# TIDA-010954-Output.net
KiCad netlist of a schematic drawn in Altium Designer
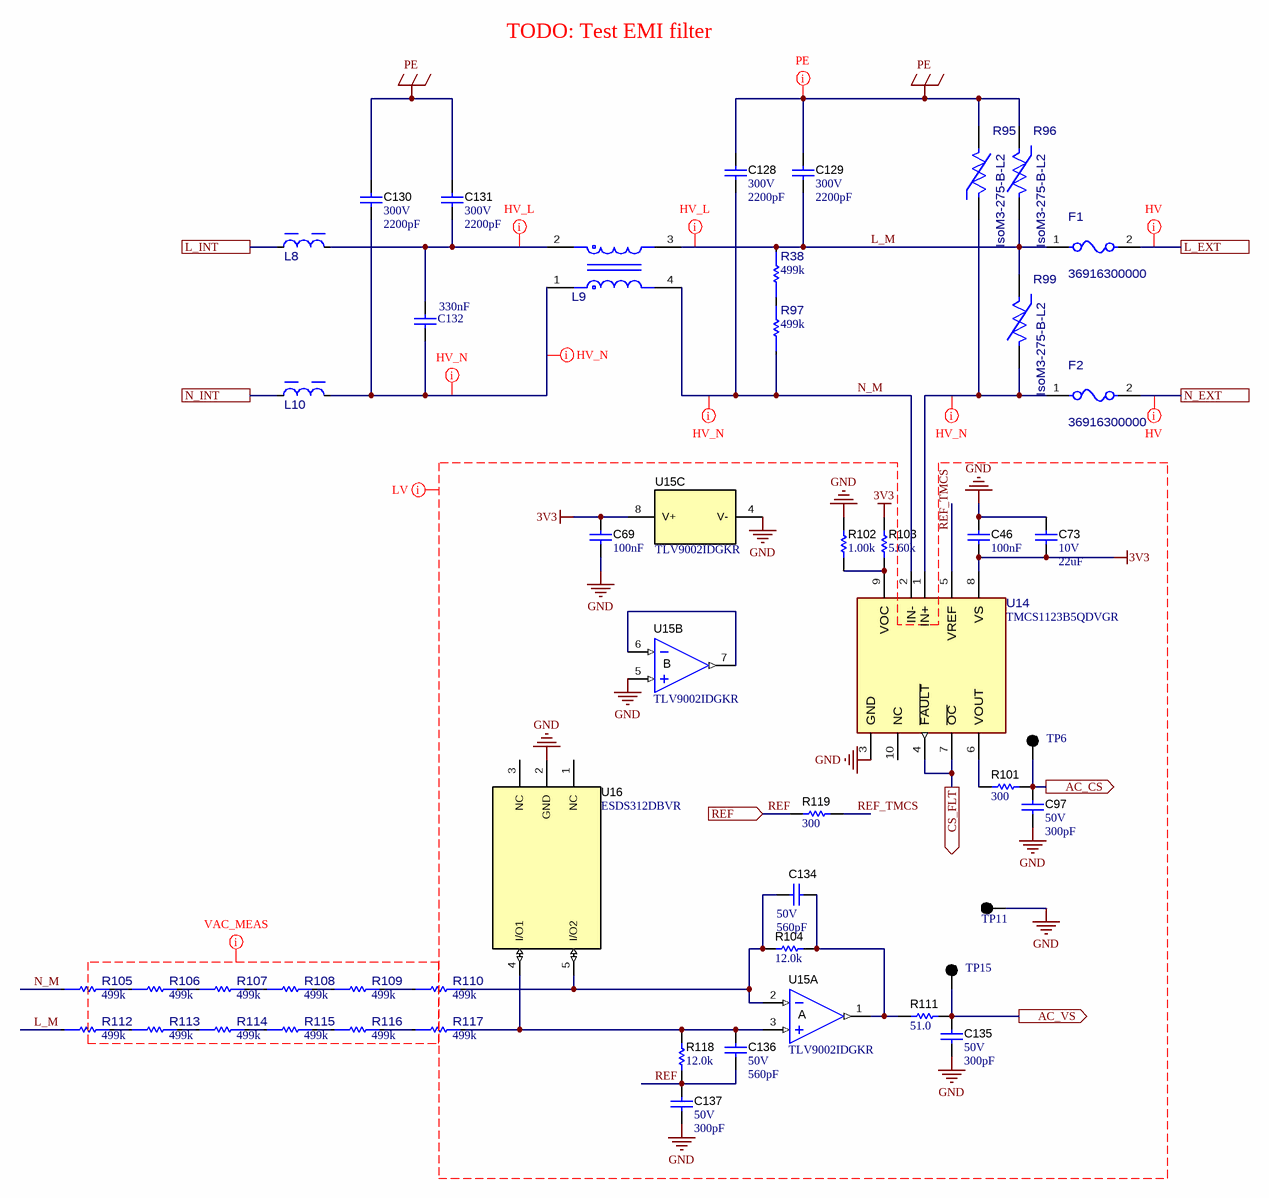
[diagram p0: TIDA-010954-Output.SchDoc]

(export (version "E")
  (design (tool "Eeschema 10.0.6"))
  (components
    (comp (ref "C46")
      (value "CGA3E2X7R1E104K080AA")
      (footprint "0603")
      (description "CAP, CERM, 0.1 uF, 25 V, +/- 10%, X7R, AEC-Q200 Grade 1, 0603")
      (fields
        (field (name "MANUFACTURER") "TDK")
        (field (name "CAP_F") "100nF")
        (field (name "PUBLISHER") "Texas Instruments")
      )
      (libsource (lib "Altium Vault - TI") (part "Capacitor"))
    )
    (comp (ref "C69")
      (value "CGA3E2X7R1E104K080AA")
      (footprint "0603")
      (description "CAP, CERM, 0.1 uF, 25 V, +/- 10%, X7R, AEC-Q200 Grade 1, 0603")
      (fields
        (field (name "MANUFACTURER") "TDK")
        (field (name "CAP_F") "100nF")
        (field (name "PUBLISHER") "Texas Instruments")
      )
      (libsource (lib "Altium Vault - TI") (part "Capacitor"))
    )
    (comp (ref "C73")
      (value "GRM31CR71A226KE15L")
      (footprint "1206_180")
      (description "CAP, CERM, 22 uF, 10 V, +/- 10%, X7R, 1206")
      (fields
        (field (name "MANUFACTURER") "MuRata")
        (field (name "VDC_V") "10V")
        (field (name "VALUEDISPLAYED") "22uF")
        (field (name "PUBLISHER") "Texas Instruments")
      )
      (libsource (lib "Altium Vault - TI") (part "Capacitor"))
    )
    (comp (ref "C97")
      (value "GRM1885C1H301JA01D")
      (footprint "0603")
      (description "CAP, CERM, 300 pF, 50 V, +/- 5%, C0G/NP0, 0603")
      (fields
        (field (name "MANUFACTURER") "MuRata")
        (field (name "VDC_V") "50V")
        (field (name "VALUEDISPLAYED") "300pF")
        (field (name "PUBLISHER") "Texas Instruments")
      )
      (libsource (lib "Altium Vault - TI") (part "Capacitor"))
    )
    (comp (ref "C128")
      (value "DE6E3KJ222MN3A")
      (footprint "E_900x700x900")
      (description "CAP, CERM, 2200 pF, 300 V, +/- 20%, E, TH, 2- Leads, Body 9x7mm, Pin Spacing 7.5mm")
      (fields
        (field (name "MANUFACTURER") "MuRata")
        (field (name "VDC_V") "300V")
        (field (name "VALUEDISPLAYED") "2200pF")
        (field (name "PUBLISHER") "Texas Instruments")
      )
      (libsource (lib "Altium Vault - TI") (part "Capacitor"))
    )
    (comp (ref "C129")
      (value "DE6E3KJ222MN3A")
      (footprint "E_900x700x900")
      (description "CAP, CERM, 2200 pF, 300 V, +/- 20%, E, TH, 2- Leads, Body 9x7mm, Pin Spacing 7.5mm")
      (fields
        (field (name "MANUFACTURER") "MuRata")
        (field (name "VDC_V") "300V")
        (field (name "VALUEDISPLAYED") "2200pF")
        (field (name "PUBLISHER") "Texas Instruments")
      )
      (libsource (lib "Altium Vault - TI") (part "Capacitor"))
    )
    (comp (ref "C130")
      (value "DE6E3KJ222MN3A")
      (footprint "E_900x700x900")
      (description "CAP, CERM, 2200 pF, 300 V, +/- 20%, E, TH, 2- Leads, Body 9x7mm, Pin Spacing 7.5mm")
      (fields
        (field (name "MANUFACTURER") "MuRata")
        (field (name "VDC_V") "300V")
        (field (name "VALUEDISPLAYED") "2200pF")
        (field (name "PUBLISHER") "Texas Instruments")
      )
      (libsource (lib "Altium Vault - TI") (part "Capacitor"))
    )
    (comp (ref "C131")
      (value "DE6E3KJ222MN3A")
      (footprint "E_900x700x900")
      (description "CAP, CERM, 2200 pF, 300 V, +/- 20%, E, TH, 2- Leads, Body 9x7mm, Pin Spacing 7.5mm")
      (fields
        (field (name "MANUFACTURER") "MuRata")
        (field (name "VDC_V") "300V")
        (field (name "VALUEDISPLAYED") "2200pF")
        (field (name "PUBLISHER") "Texas Instruments")
      )
      (libsource (lib "Altium Vault - TI") (part "Capacitor"))
    )
    (comp (ref "C132")
      (value "890324025034CS")
      (footprint "WCAP-FTX2_L18W8.5H14.5_CS")
      (description "WCAP-FTX2 Film Capacitor, THT, L18 x W8.5 x H14.5mm, 330nF, 275V")
      (fields (field (name "CAP_F") "330nF") (field (name "MANUFACTURER") "Wurth Elektronik"))
      (libsource (lib "Altium Vault - TI") (part "890764429002CS"))
    )
    (comp (ref "C134")
      (value "GRM1885C1H561JA01D")
      (footprint "0603")
      (description "CAP, CERM, 560 pF, 50 V, +/- 5%, C0G/NP0, 0603")
      (fields
        (field (name "MANUFACTURER") "MuRata")
        (field (name "VDC_V") "50V")
        (field (name "VALUEDISPLAYED") "560pF")
        (field (name "PUBLISHER") "Texas Instruments")
      )
      (libsource (lib "Altium Vault - TI") (part "Capacitor"))
    )
    (comp (ref "C135")
      (value "GRM1885C1H301JA01D")
      (footprint "0603")
      (description "CAP, CERM, 300 pF, 50 V, +/- 5%, C0G/NP0, 0603")
      (fields
        (field (name "MANUFACTURER") "MuRata")
        (field (name "VDC_V") "50V")
        (field (name "VALUEDISPLAYED") "300pF")
        (field (name "PUBLISHER") "Texas Instruments")
      )
      (libsource (lib "Altium Vault - TI") (part "Capacitor"))
    )
    (comp (ref "C136")
      (value "GRM1885C1H561JA01D")
      (footprint "0603")
      (description "CAP, CERM, 560 pF, 50 V, +/- 5%, C0G/NP0, 0603")
      (fields
        (field (name "MANUFACTURER") "MuRata")
        (field (name "VDC_V") "50V")
        (field (name "VALUEDISPLAYED") "560pF")
        (field (name "PUBLISHER") "Texas Instruments")
      )
      (libsource (lib "Altium Vault - TI") (part "Capacitor"))
    )
    (comp (ref "C137")
      (value "GRM1885C1H301JA01D")
      (footprint "0603")
      (description "CAP, CERM, 300 pF, 50 V, +/- 5%, C0G/NP0, 0603")
      (fields
        (field (name "MANUFACTURER") "MuRata")
        (field (name "VDC_V") "50V")
        (field (name "VALUEDISPLAYED") "300pF")
        (field (name "PUBLISHER") "Texas Instruments")
      )
      (libsource (lib "Altium Vault - TI") (part "Capacitor"))
    )
    (comp (ref "F1")
      (value "36916300000")
      (footprint "FP-36916300000_RADIAL-MFG")
      (description "6.3 A 300 V AC DC Fuse Board Mount (Cartridge Style Excluded) Through Hole Radial, Box")
      (fields
        (field (name "MANUFACTURER") "Littelfuse Inc")
        (field (name "DIGIKEY PART NUMBER") "F5465CT-ND")
      )
      (libsource (lib "Altium Vault - TI") (part "SYM-36916300000"))
    )
    (comp (ref "F2")
      (value "36916300000")
      (footprint "FP-36916300000_RADIAL-MFG")
      (description "6.3 A 300 V AC DC Fuse Board Mount (Cartridge Style Excluded) Through Hole Radial, Box")
      (fields
        (field (name "MANUFACTURER") "Littelfuse Inc")
        (field (name "DIGIKEY PART NUMBER") "F5465CT-ND")
      )
      (libsource (lib "Altium Vault - TI") (part "SYM-36916300000"))
    )
    (comp (ref "L8")
      (value "7443551221")
      (footprint "FP-7443551221_SMD_IND_12MM8_12MM8-MFG")
      (description "22 µH Shielded Wirewound Inductor 6 A 24.7mOhm Nonstandard")
      (fields
        (field (name "MANUFACTURER") "Wurth Electronics")
        (field (name "MOUSER PART NUMBER") "710-7443551221")
      )
      (libsource (lib "Altium Vault - TI") (part "SYM-7443551221"))
    )
    (comp (ref "L9")
      (value "7448025003")
      (footprint "FP-7448025003_PTH_COMMON_CHOKE-MFG")
      (description "2.5 mH @ 10 kHz 2 Line Common Mode Choke Through Hole 5A DCR 15mOhm")
      (fields
        (field (name "MOUSER PART NUMBER") "710-7448025003")
        (field (name "DIGIKEY PART NUMBER") "732-13592-ND")
      )
      (libsource (lib "Altium Vault - TI") (part "SYM-7448025003"))
    )
    (comp (ref "L10")
      (value "7443551221")
      (footprint "FP-7443551221_SMD_IND_12MM8_12MM8-MFG")
      (description "22 µH Shielded Wirewound Inductor 6 A 24.7mOhm Nonstandard")
      (fields
        (field (name "MANUFACTURER") "Wurth Electronics")
        (field (name "MOUSER PART NUMBER") "710-7443551221")
      )
      (libsource (lib "Altium Vault - TI") (part "SYM-7443551221"))
    )
    (comp (ref "R38")
      (value "499k")
      (footprint "FP-ERJP08D4993V_1206-MFG")
      (fields
        (field (name "MANUFACTURER") "Panasonic")
        (field (name "PARTNUMBER") "ERJP08D4993V")
        (field (name "DIGIKEY PART NUMBER") "ERJ-P08D4993V-ND")
      )
      (libsource (lib "Altium Vault - TI") (part "SYM-ERJP08D4993V"))
    )
    (comp (ref "R95")
      (value "IsoM3-275-B-L2")
      (footprint "FP-IsoM3-275-B-L2_RADIAL-MFG")
      (description "3 kA Varistor 1 Circuit Through Hole Disc 13.2mm")
      (fields
        (field (name "DIGIKEY PART NUMBER") "118-ISOM3-275-B-L2-ND")
        (field (name "MANUFACTURER") "Bourns")
      )
      (libsource (lib "Altium Vault - TI") (part "SYM-IsoM3-275-B-L2"))
    )
    (comp (ref "R96")
      (value "IsoM3-275-B-L2")
      (footprint "FP-IsoM3-275-B-L2_RADIAL-MFG")
      (description "3 kA Varistor 1 Circuit Through Hole Disc 13.2mm")
      (fields
        (field (name "DIGIKEY PART NUMBER") "118-ISOM3-275-B-L2-ND")
        (field (name "MANUFACTURER") "Bourns")
      )
      (libsource (lib "Altium Vault - TI") (part "SYM-IsoM3-275-B-L2"))
    )
    (comp (ref "R97")
      (value "499k")
      (footprint "FP-ERJP08D4993V_1206-MFG")
      (fields
        (field (name "MANUFACTURER") "Panasonic")
        (field (name "PARTNUMBER") "ERJP08D4993V")
        (field (name "DIGIKEY PART NUMBER") "ERJ-P08D4993V-ND")
      )
      (libsource (lib "Altium Vault - TI") (part "SYM-ERJP08D4993V"))
    )
    (comp (ref "R99")
      (value "IsoM3-275-B-L2")
      (footprint "FP-IsoM3-275-B-L2_RADIAL-MFG")
      (description "3 kA Varistor 1 Circuit Through Hole Disc 13.2mm")
      (fields
        (field (name "DIGIKEY PART NUMBER") "118-ISOM3-275-B-L2-ND")
        (field (name "MANUFACTURER") "Bourns")
      )
      (libsource (lib "Altium Vault - TI") (part "SYM-IsoM3-275-B-L2"))
    )
    (comp (ref "R101")
      (value "RC0603FR-07300RL")
      (footprint "0603")
      (description "RES, 300, 1%, 0.1 W, 0603")
      (fields (field (name "MANUFACTURER") "Yageo") (field (name "VALUEDISPLAYED") "300"))
      (libsource (lib "Altium Vault - TI") (part "Resistor"))
    )
    (comp (ref "R102")
      (value "RC0603FR-071KL")
      (footprint "0603")
      (description "RES, 1.00 k, 1%, 0.1 W, 0603")
      (fields (field (name "MANUFACTURER") "Yageo") (field (name "VALUEDISPLAYED") "1.00k"))
      (libsource (lib "Altium Vault - TI") (part "Resistor"))
    )
    (comp (ref "R103")
      (value "RC0603FR-075K6L")
      (footprint "0603")
      (description "RES, 5.60 k, 1%, 0.1 W, 0603")
      (fields (field (name "MANUFACTURER") "Yageo") (field (name "VALUEDISPLAYED") "5.60k"))
      (libsource (lib "Altium Vault - TI") (part "Resistor"))
    )
    (comp (ref "R104")
      (value "RT0603BRD0712KL")
      (footprint "0603")
      (description "RES, 12.0 k, 0.1%, 0.1 W, 0603")
      (fields
        (field (name "MANUFACTURER") "Yageo America")
        (field (name "VALUEDISPLAYED") "12.0k")
        (field (name "PUBLISHER") "Texas Instruments")
      )
      (libsource (lib "Altium Vault - TI") (part "Resistor"))
    )
    (comp (ref "R105")
      (value "499k")
      (footprint "FP-ERJP08D4993V_1206-MFG")
      (fields
        (field (name "MANUFACTURER") "Panasonic")
        (field (name "PARTNUMBER") "ERJP08D4993V")
        (field (name "DIGIKEY PART NUMBER") "ERJ-P08D4993V-ND")
      )
      (libsource (lib "Altium Vault - TI") (part "SYM-ERJP08D4993V"))
    )
    (comp (ref "R106")
      (value "499k")
      (footprint "FP-ERJP08D4993V_1206-MFG")
      (fields
        (field (name "MANUFACTURER") "Panasonic")
        (field (name "PARTNUMBER") "ERJP08D4993V")
        (field (name "DIGIKEY PART NUMBER") "ERJ-P08D4993V-ND")
      )
      (libsource (lib "Altium Vault - TI") (part "SYM-ERJP08D4993V"))
    )
    (comp (ref "R107")
      (value "499k")
      (footprint "FP-ERJP08D4993V_1206-MFG")
      (fields
        (field (name "MANUFACTURER") "Panasonic")
        (field (name "PARTNUMBER") "ERJP08D4993V")
        (field (name "DIGIKEY PART NUMBER") "ERJ-P08D4993V-ND")
      )
      (libsource (lib "Altium Vault - TI") (part "SYM-ERJP08D4993V"))
    )
    (comp (ref "R108")
      (value "499k")
      (footprint "FP-ERJP08D4993V_1206-MFG")
      (fields
        (field (name "MANUFACTURER") "Panasonic")
        (field (name "PARTNUMBER") "ERJP08D4993V")
        (field (name "DIGIKEY PART NUMBER") "ERJ-P08D4993V-ND")
      )
      (libsource (lib "Altium Vault - TI") (part "SYM-ERJP08D4993V"))
    )
    (comp (ref "R109")
      (value "499k")
      (footprint "FP-ERJP08D4993V_1206-MFG")
      (fields
        (field (name "MANUFACTURER") "Panasonic")
        (field (name "PARTNUMBER") "ERJP08D4993V")
        (field (name "DIGIKEY PART NUMBER") "ERJ-P08D4993V-ND")
      )
      (libsource (lib "Altium Vault - TI") (part "SYM-ERJP08D4993V"))
    )
    (comp (ref "R110")
      (value "499k")
      (footprint "FP-ERJP08D4993V_1206-MFG")
      (fields
        (field (name "MANUFACTURER") "Panasonic")
        (field (name "PARTNUMBER") "ERJP08D4993V")
        (field (name "DIGIKEY PART NUMBER") "ERJ-P08D4993V-ND")
      )
      (libsource (lib "Altium Vault - TI") (part "SYM-ERJP08D4993V"))
    )
    (comp (ref "R111")
      (value "RC0603FR-0751RL")
      (footprint "0603")
      (description "RES, 51.0, 1%, 0.1 W, 0603")
      (fields (field (name "MANUFACTURER") "Yageo") (field (name "VALUEDISPLAYED") "51.0"))
      (libsource (lib "Altium Vault - TI") (part "Resistor"))
    )
    (comp (ref "R112")
      (value "499k")
      (footprint "FP-ERJP08D4993V_1206-MFG")
      (fields
        (field (name "MANUFACTURER") "Panasonic")
        (field (name "PARTNUMBER") "ERJP08D4993V")
        (field (name "DIGIKEY PART NUMBER") "ERJ-P08D4993V-ND")
      )
      (libsource (lib "Altium Vault - TI") (part "SYM-ERJP08D4993V"))
    )
    (comp (ref "R113")
      (value "499k")
      (footprint "FP-ERJP08D4993V_1206-MFG")
      (fields
        (field (name "MANUFACTURER") "Panasonic")
        (field (name "PARTNUMBER") "ERJP08D4993V")
        (field (name "DIGIKEY PART NUMBER") "ERJ-P08D4993V-ND")
      )
      (libsource (lib "Altium Vault - TI") (part "SYM-ERJP08D4993V"))
    )
    (comp (ref "R114")
      (value "499k")
      (footprint "FP-ERJP08D4993V_1206-MFG")
      (fields
        (field (name "MANUFACTURER") "Panasonic")
        (field (name "PARTNUMBER") "ERJP08D4993V")
        (field (name "DIGIKEY PART NUMBER") "ERJ-P08D4993V-ND")
      )
      (libsource (lib "Altium Vault - TI") (part "SYM-ERJP08D4993V"))
    )
    (comp (ref "R115")
      (value "499k")
      (footprint "FP-ERJP08D4993V_1206-MFG")
      (fields
        (field (name "MANUFACTURER") "Panasonic")
        (field (name "PARTNUMBER") "ERJP08D4993V")
        (field (name "DIGIKEY PART NUMBER") "ERJ-P08D4993V-ND")
      )
      (libsource (lib "Altium Vault - TI") (part "SYM-ERJP08D4993V"))
    )
    (comp (ref "R116")
      (value "499k")
      (footprint "FP-ERJP08D4993V_1206-MFG")
      (fields
        (field (name "MANUFACTURER") "Panasonic")
        (field (name "PARTNUMBER") "ERJP08D4993V")
        (field (name "DIGIKEY PART NUMBER") "ERJ-P08D4993V-ND")
      )
      (libsource (lib "Altium Vault - TI") (part "SYM-ERJP08D4993V"))
    )
    (comp (ref "R117")
      (value "499k")
      (footprint "FP-ERJP08D4993V_1206-MFG")
      (fields
        (field (name "MANUFACTURER") "Panasonic")
        (field (name "PARTNUMBER") "ERJP08D4993V")
        (field (name "DIGIKEY PART NUMBER") "ERJ-P08D4993V-ND")
      )
      (libsource (lib "Altium Vault - TI") (part "SYM-ERJP08D4993V"))
    )
    (comp (ref "R118")
      (value "RT0603BRD0712KL")
      (footprint "0603")
      (description "RES, 12.0 k, 0.1%, 0.1 W, 0603")
      (fields
        (field (name "MANUFACTURER") "Yageo America")
        (field (name "VALUEDISPLAYED") "12.0k")
        (field (name "PUBLISHER") "Texas Instruments")
      )
      (libsource (lib "Altium Vault - TI") (part "Resistor"))
    )
    (comp (ref "R119")
      (value "RC0603FR-07300RL")
      (footprint "0603")
      (description "RES, 300, 1%, 0.1 W, 0603")
      (fields (field (name "MANUFACTURER") "Yageo") (field (name "VALUEDISPLAYED") "300"))
      (libsource (lib "Altium Vault - TI") (part "Resistor"))
    )
    (comp (ref "TP6")
      (value "5011")
      (footprint "Keystone5011")
      (description "Test Point, Multipurpose, Black, TH")
      (fields
        (field (name "MANUFACTURER") "Keystone Electronics")
        (field (name "PUBLISHER") "Texas Instruments")
      )
      (libsource (lib "Altium Vault - TI") (part "5011"))
    )
    (comp (ref "TP11")
      (value "5011")
      (footprint "Keystone5011")
      (description "Test Point, Multipurpose, Black, TH")
      (fields
        (field (name "MANUFACTURER") "Keystone Electronics")
        (field (name "PUBLISHER") "Texas Instruments")
      )
      (libsource (lib "Altium Vault - TI") (part "5011"))
    )
    (comp (ref "TP15")
      (value "5011")
      (footprint "Keystone5011")
      (description "Test Point, Multipurpose, Black, TH")
      (fields
        (field (name "MANUFACTURER") "Keystone Electronics")
        (field (name "PUBLISHER") "Texas Instruments")
      )
      (libsource (lib "Altium Vault - TI") (part "5011"))
    )
    (comp (ref "U14")
      (value "TMCS1123B5QDVGR")
      (footprint "DVG0010A-MFG")
      (fields (field (name "PARTNUMBER") "TMCS1123B5QDVGR") (field (name "MANUFACTURER") "Texas Instruments"))
      (libsource (lib "Altium Vault - TI") (part "SYM-TMCS1123B5QDVGR"))
    )
    (comp (ref "U15")
      (value "TLV9002IDGKR")
      (footprint "DGK0008A_N")
      (fields
        (field (name "ALTERNATE PARTNUMBER") "TLV2333IDGKT")
        (field (name "MANUFACTURER") "Texas Instruments")
        (field (name "PARTNUMBER") "TLV9002IDGKR")
      )
      (libsource (lib "Altium Vault - TI") (part "Opamp_Dual"))
    )
    (comp (ref "U16")
      (value "ESDS312DBVR")
      (footprint "DBV0005A_N")
      (description "3.6V Data-Line Surge and 30kV ESD Protection Diode Array, DBV0005A (SOT-23-5)")
      (fields (field (name "PARTNUMBER") "ESDS312DBVR") (field (name "MANUFACTURER") "Texas Instruments"))
      (libsource (lib "Altium Vault - TI") (part "ESDS03812"))
    )
  )
  (nets
    (net (code "1") (name "/AC_CS") (class "Default")
      (node (ref "C97") (pin "1") (pinfunction "1_1") (pintype "passive"))
      (node (ref "R101") (pin "1") (pinfunction "1_1") (pintype "passive"))
      (node (ref "TP6") (pin "1") (pintype "passive"))
    )
    (net (code "2") (name "/AC_VS") (class "Default")
      (node (ref "C135") (pin "1") (pinfunction "1_1") (pintype "passive"))
      (node (ref "R111") (pin "2") (pinfunction "2_2") (pintype "passive"))
      (node (ref "TP15") (pin "1") (pintype "passive"))
    )
    (net (code "3") (name "/CS_FLT") (class "Default")
      (node (ref "U14") (pin "4") (pinfunction "~{FAULT}_4") (pintype "output"))
      (node (ref "U14") (pin "7") (pinfunction "~{OC}_7") (pintype "open_collector"))
    )
    (net (code "4") (name "/L_EXT") (class "Default")
      (node (ref "F1") (pin "2") (pinfunction "2_2") (pintype "passive"))
    )
    (net (code "5") (name "/L_INT") (class "Default")
      (node (ref "L8") (pin "1") (pinfunction "1_1") (pintype "passive"))
    )
    (net (code "6") (name "/L_M") (class "Default")
      (node (ref "C129") (pin "2") (pinfunction "2_2") (pintype "passive"))
      (node (ref "F1") (pin "1") (pinfunction "1_1") (pintype "passive"))
      (node (ref "L9") (pin "3") (pinfunction "3_3") (pintype "passive"))
      (node (ref "R112") (pin "1") (pinfunction "1_1") (pintype "passive"))
      (node (ref "R38") (pin "2") (pinfunction "2_2") (pintype "passive"))
      (node (ref "R96") (pin "1") (pinfunction "1_1") (pintype "passive"))
      (node (ref "R99") (pin "2") (pinfunction "2_2") (pintype "passive"))
    )
    (net (code "7") (name "/N_EXT") (class "Default")
      (node (ref "F2") (pin "2") (pinfunction "2_2") (pintype "passive"))
    )
    (net (code "8") (name "/N_INT") (class "Default")
      (node (ref "L10") (pin "1") (pinfunction "1_1") (pintype "passive"))
    )
    (net (code "9") (name "/N_M") (class "Default")
      (node (ref "C128") (pin "1") (pinfunction "1_1") (pintype "passive"))
      (node (ref "L9") (pin "4") (pinfunction "4_4") (pintype "passive"))
      (node (ref "R105") (pin "1") (pinfunction "1_1") (pintype "passive"))
      (node (ref "R97") (pin "1") (pinfunction "1_1") (pintype "passive"))
      (node (ref "U14") (pin "2") (pinfunction "IN-_2") (pintype "passive"))
    )
    (net (code "10") (name "/REF") (class "Default")
      (node (ref "C136") (pin "2") (pinfunction "2_2") (pintype "passive"))
      (node (ref "C137") (pin "1") (pinfunction "1_1") (pintype "passive"))
      (node (ref "R118") (pin "1") (pinfunction "1_1") (pintype "passive"))
      (node (ref "R119") (pin "2") (pinfunction "2_2") (pintype "passive"))
    )
    (net (code "11") (name "/REF_TMCS") (class "Default")
      (node (ref "R119") (pin "1") (pinfunction "1_1") (pintype "passive"))
      (node (ref "U14") (pin "5") (pinfunction "VREF_5") (pintype "passive"))
    )
    (net (code "12") (name "3V3") (class "Default")
      (node (ref "C46") (pin "1") (pinfunction "1_1") (pintype "passive"))
      (node (ref "C69") (pin "2") (pinfunction "2_2") (pintype "passive"))
      (node (ref "C73") (pin "2") (pinfunction "2_2") (pintype "passive"))
      (node (ref "R103") (pin "1") (pinfunction "1_1") (pintype "passive"))
      (node (ref "U14") (pin "8") (pinfunction "VS_8") (pintype "power_in"))
      (node (ref "U15") (pin "8") (pinfunction "V+_8") (pintype "power_in"))
    )
    (net (code "13") (name "GND") (class "Default")
      (node (ref "C135") (pin "2") (pinfunction "2_2") (pintype "passive"))
      (node (ref "C137") (pin "2") (pinfunction "2_2") (pintype "passive"))
      (node (ref "C46") (pin "2") (pinfunction "2_2") (pintype "passive"))
      (node (ref "C69") (pin "1") (pinfunction "1_1") (pintype "passive"))
      (node (ref "C73") (pin "1") (pinfunction "1_1") (pintype "passive"))
      (node (ref "C97") (pin "2") (pinfunction "2_2") (pintype "passive"))
      (node (ref "R102") (pin "1") (pinfunction "1_1") (pintype "passive"))
      (node (ref "TP11") (pin "1") (pintype "passive"))
      (node (ref "U14") (pin "3") (pinfunction "GND_3") (pintype "power_in"))
      (node (ref "U15") (pin "4") (pinfunction "V-_4") (pintype "power_in"))
      (node (ref "U15") (pin "5") (pinfunction "IN+_5") (pintype "input"))
      (node (ref "U16") (pin "2") (pinfunction "GND_2") (pintype "power_in"))
    )
    (net (code "14") (name "Net-(C130-Pad2)") (class "Default")
      (node (ref "C130") (pin "2") (pinfunction "2_2") (pintype "passive"))
      (node (ref "C132") (pin "1") (pinfunction "1_1") (pintype "passive"))
      (node (ref "L10") (pin "2") (pinfunction "2_2") (pintype "passive"))
      (node (ref "L9") (pin "1") (pinfunction "1_1") (pintype "passive"))
    )
    (net (code "15") (name "Net-(C131-Pad1)") (class "Default")
      (node (ref "C131") (pin "1") (pinfunction "1_1") (pintype "passive"))
      (node (ref "C132") (pin "2") (pinfunction "2_2") (pintype "passive"))
      (node (ref "L8") (pin "2") (pinfunction "2_2") (pintype "passive"))
      (node (ref "L9") (pin "2") (pinfunction "2_2") (pintype "passive"))
    )
    (net (code "16") (name "Net-(R38-Pad1)") (class "Default")
      (node (ref "R38") (pin "1") (pinfunction "1_1") (pintype "passive"))
      (node (ref "R97") (pin "2") (pinfunction "2_2") (pintype "passive"))
    )
    (net (code "17") (name "Net-(R105-Pad2)") (class "Default")
      (node (ref "R105") (pin "2") (pinfunction "2_2") (pintype "passive"))
      (node (ref "R106") (pin "1") (pinfunction "1_1") (pintype "passive"))
    )
    (net (code "18") (name "Net-(R106-Pad2)") (class "Default")
      (node (ref "R106") (pin "2") (pinfunction "2_2") (pintype "passive"))
      (node (ref "R107") (pin "1") (pinfunction "1_1") (pintype "passive"))
    )
    (net (code "19") (name "Net-(R107-Pad2)") (class "Default")
      (node (ref "R107") (pin "2") (pinfunction "2_2") (pintype "passive"))
      (node (ref "R108") (pin "1") (pinfunction "1_1") (pintype "passive"))
    )
    (net (code "20") (name "Net-(R108-Pad2)") (class "Default")
      (node (ref "R108") (pin "2") (pinfunction "2_2") (pintype "passive"))
      (node (ref "R109") (pin "1") (pinfunction "1_1") (pintype "passive"))
    )
    (net (code "21") (name "Net-(R109-Pad2)") (class "Default")
      (node (ref "R109") (pin "2") (pinfunction "2_2") (pintype "passive"))
      (node (ref "R110") (pin "1") (pinfunction "1_1") (pintype "passive"))
    )
    (net (code "22") (name "Net-(R112-Pad2)") (class "Default")
      (node (ref "R112") (pin "2") (pinfunction "2_2") (pintype "passive"))
      (node (ref "R113") (pin "1") (pinfunction "1_1") (pintype "passive"))
    )
    (net (code "23") (name "Net-(R113-Pad2)") (class "Default")
      (node (ref "R113") (pin "2") (pinfunction "2_2") (pintype "passive"))
      (node (ref "R114") (pin "1") (pinfunction "1_1") (pintype "passive"))
    )
    (net (code "24") (name "Net-(R114-Pad2)") (class "Default")
      (node (ref "R114") (pin "2") (pinfunction "2_2") (pintype "passive"))
      (node (ref "R115") (pin "1") (pinfunction "1_1") (pintype "passive"))
    )
    (net (code "25") (name "Net-(R115-Pad2)") (class "Default")
      (node (ref "R115") (pin "2") (pinfunction "2_2") (pintype "passive"))
      (node (ref "R116") (pin "1") (pinfunction "1_1") (pintype "passive"))
    )
    (net (code "26") (name "Net-(R116-Pad2)") (class "Default")
      (node (ref "R116") (pin "2") (pinfunction "2_2") (pintype "passive"))
      (node (ref "R117") (pin "1") (pinfunction "1_1") (pintype "passive"))
    )
    (net (code "27") (name "Net-(U14-IN+)") (class "Default")
      (node (ref "F2") (pin "1") (pinfunction "1_1") (pintype "passive"))
      (node (ref "R95") (pin "2") (pinfunction "2_2") (pintype "passive"))
      (node (ref "R99") (pin "1") (pinfunction "1_1") (pintype "passive"))
      (node (ref "U14") (pin "1") (pinfunction "IN+_1") (pintype "passive"))
    )
    (net (code "28") (name "Net-(U14-VOC)") (class "Default")
      (node (ref "R102") (pin "2") (pinfunction "2_2") (pintype "passive"))
      (node (ref "R103") (pin "2") (pinfunction "2_2") (pintype "passive"))
      (node (ref "U14") (pin "9") (pinfunction "VOC_9") (pintype "passive"))
    )
    (net (code "29") (name "Net-(U14-VOUT)") (class "Default")
      (node (ref "R101") (pin "2") (pinfunction "2_2") (pintype "passive"))
      (node (ref "U14") (pin "6") (pinfunction "VOUT_6") (pintype "passive"))
    )
    (net (code "30") (name "Net-(U15A-IN+)") (class "Default")
      (node (ref "C136") (pin "1") (pinfunction "1_1") (pintype "passive"))
      (node (ref "R117") (pin "2") (pinfunction "2_2") (pintype "passive"))
      (node (ref "R118") (pin "2") (pinfunction "2_2") (pintype "passive"))
      (node (ref "U15") (pin "3") (pinfunction "IN+_3") (pintype "input"))
      (node (ref "U16") (pin "4") (pinfunction "I/O1_4") (pintype "bidirectional"))
    )
    (net (code "31") (name "Net-(U15A-IN-)") (class "Default")
      (node (ref "C134") (pin "2") (pinfunction "2_2") (pintype "passive"))
      (node (ref "R104") (pin "2") (pinfunction "2_2") (pintype "passive"))
      (node (ref "R110") (pin "2") (pinfunction "2_2") (pintype "passive"))
      (node (ref "U15") (pin "2") (pinfunction "IN-_2") (pintype "input"))
      (node (ref "U16") (pin "5") (pinfunction "I/O2_5") (pintype "bidirectional"))
    )
    (net (code "32") (name "Net-(U15A-OUT)") (class "Default")
      (node (ref "C134") (pin "1") (pinfunction "1_1") (pintype "passive"))
      (node (ref "R104") (pin "1") (pinfunction "1_1") (pintype "passive"))
      (node (ref "R111") (pin "1") (pinfunction "1_1") (pintype "passive"))
      (node (ref "U15") (pin "1") (pinfunction "OUT_1") (pintype "output"))
    )
    (net (code "33") (name "Net-(U15B-IN-)") (class "Default")
      (node (ref "U15") (pin "6") (pinfunction "IN-_6") (pintype "input"))
      (node (ref "U15") (pin "7") (pinfunction "OUT_7") (pintype "output"))
    )
    (net (code "34") (name "PE") (class "Default")
      (node (ref "C128") (pin "2") (pinfunction "2_2") (pintype "passive"))
      (node (ref "C129") (pin "1") (pinfunction "1_1") (pintype "passive"))
      (node (ref "C130") (pin "1") (pinfunction "1_1") (pintype "passive"))
      (node (ref "C131") (pin "2") (pinfunction "2_2") (pintype "passive"))
      (node (ref "R95") (pin "1") (pinfunction "1_1") (pintype "passive"))
      (node (ref "R96") (pin "2") (pinfunction "2_2") (pintype "passive"))
    )
    (net (code "35") (name "unconnected-(U14-NC-Pad10)") (class "Default")
      (node (ref "U14") (pin "10") (pinfunction "NC_10") (pintype "passive"))
    )
    (net (code "36") (name "unconnected-(U16-NC-Pad1)") (class "Default")
      (node (ref "U16") (pin "1") (pinfunction "NC_1") (pintype "passive"))
    )
    (net (code "37") (name "unconnected-(U16-NC-Pad3)") (class "Default")
      (node (ref "U16") (pin "3") (pinfunction "NC_3") (pintype "passive"))
    )
  )
)
